# Arduino-Pro-Mini.net
KiCad netlist of a schematic drawn in EAGLE
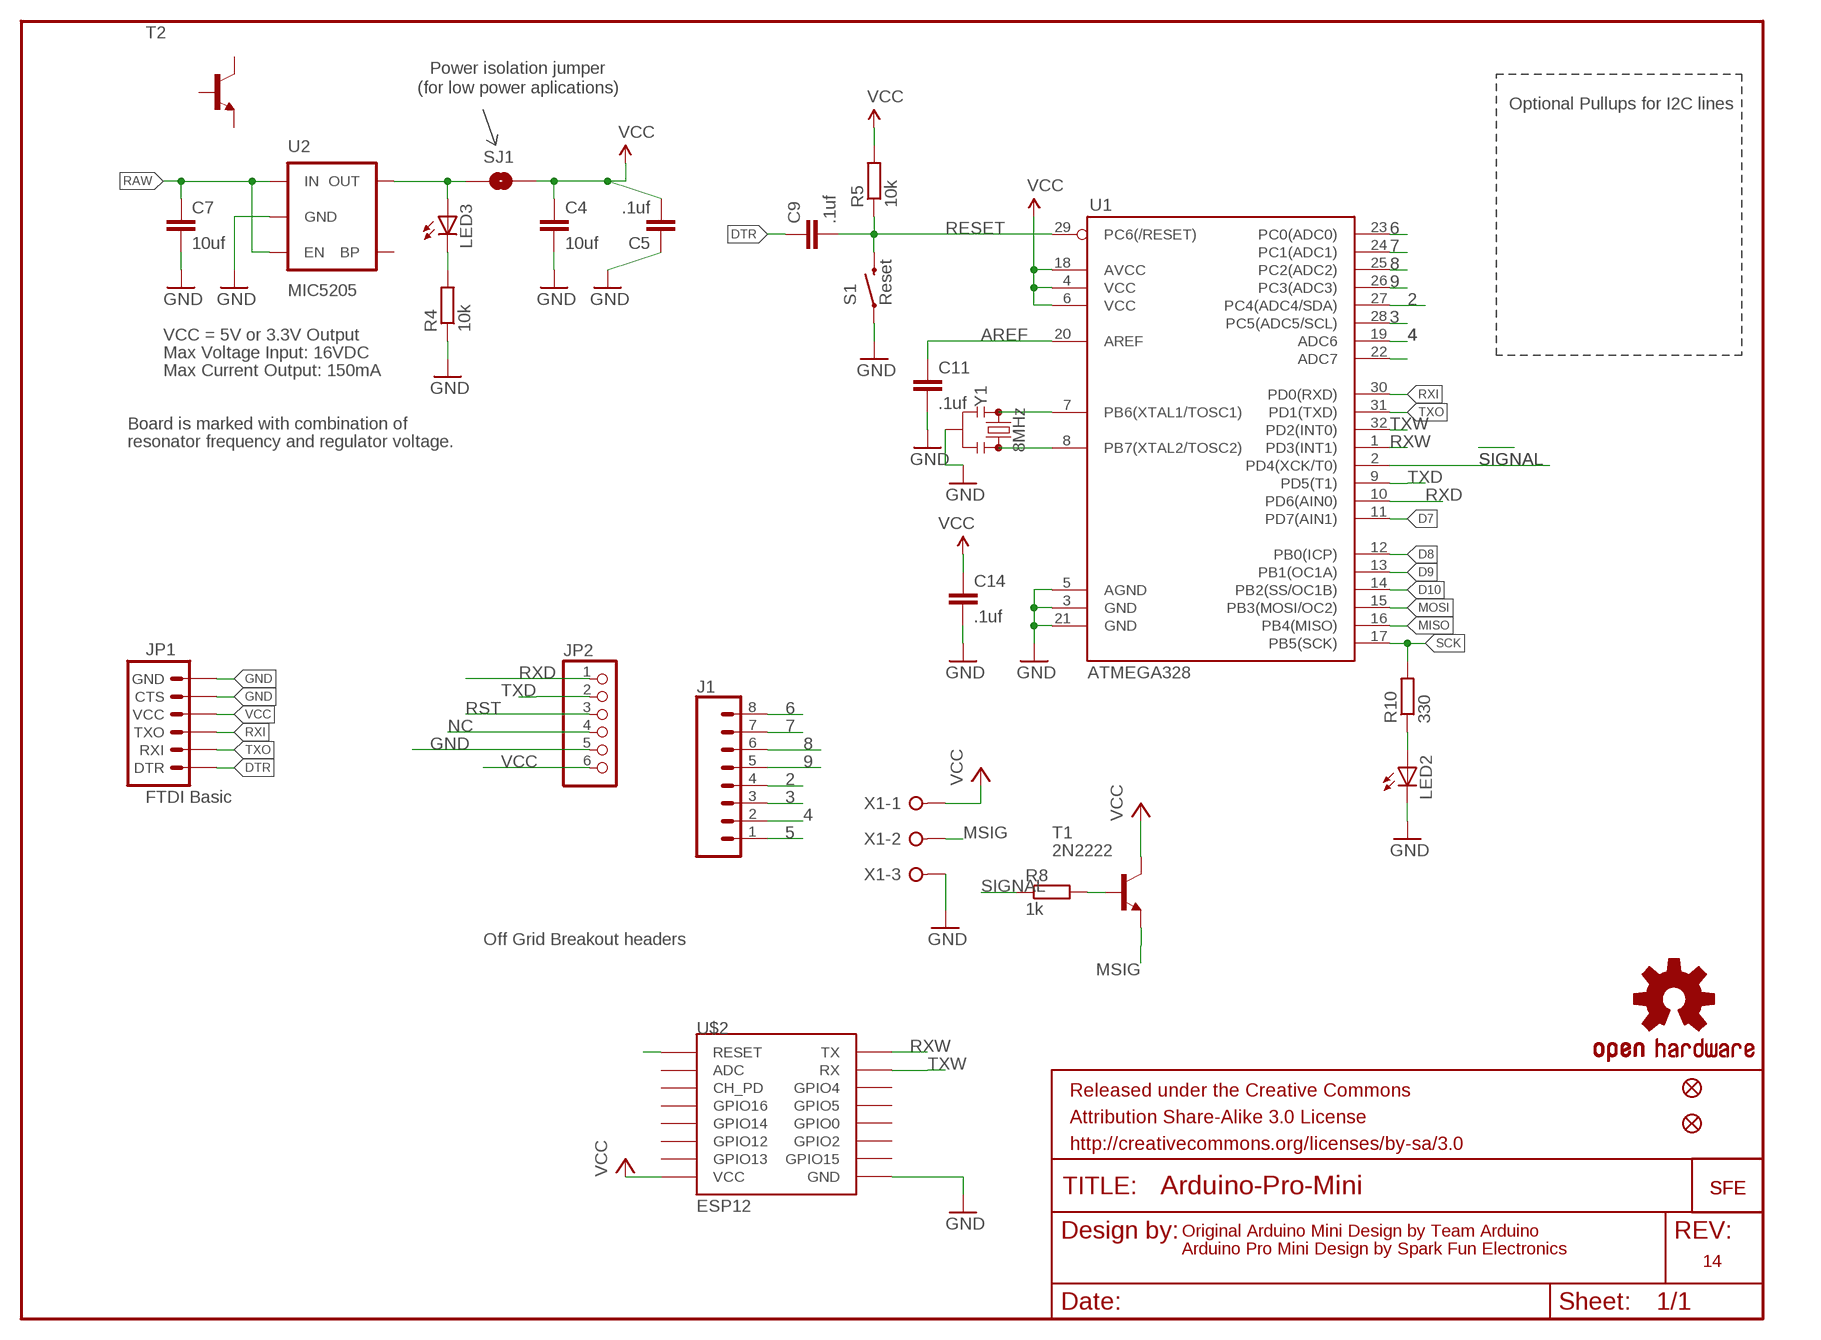
[diagram p0: schematic, sheet 1]

(export (version "E")
  (design (tool "Eeschema 10.0.6"))
  (components
    (comp (ref "C4")
      (value "10uf")
      (footprint "eagle-import:C1206")
      (libsource (lib "eagle-import") (part "C-EUC1206"))
    )
    (comp (ref "C5")
      (value ".1uf")
      (footprint "eagle-import:C1206")
      (libsource (lib "eagle-import") (part "C-EUC1206"))
    )
    (comp (ref "C7")
      (value "10uf")
      (footprint "eagle-import:C1206")
      (libsource (lib "eagle-import") (part "C-EUC1206"))
    )
    (comp (ref "C9")
      (value ".1uf")
      (footprint "eagle-import:C1206")
      (libsource (lib "eagle-import") (part "C-EUC1206"))
    )
    (comp (ref "C11")
      (value ".1uf")
      (footprint "eagle-import:C1206")
      (libsource (lib "eagle-import") (part "C-EUC1206"))
    )
    (comp (ref "C14")
      (value ".1uf")
      (footprint "eagle-import:C1206")
      (libsource (lib "eagle-import") (part "C-EUC1206"))
    )
    (comp (ref "FRAME1")
      (value "FRAME-LETTER")
      (footprint "eagle-import:CREATIVE_COMMONS")
      (libsource (lib "eagle-import") (part "FRAME-LETTER"))
    )
    (comp (ref "J1")
      (value "CONN_08\"")
      (footprint "eagle-import:1X08")
      (libsource (lib "eagle-import") (part "CONN_08{dblquote}"))
    )
    (comp (ref "JP1")
      (value "FTDI Basic")
      (footprint "eagle-import:1X06")
      (libsource (lib "eagle-import") (part "ARDUINO_SERIAL_PROGRAMPTH"))
    )
    (comp (ref "JP2")
      (value "PINHD-1X6")
      (footprint "eagle-import:1X06")
      (libsource (lib "eagle-import") (part "PINHD-1X6"))
    )
    (comp (ref "JP5")
      (value "FIDUCIALUFIDUCIAL")
      (footprint "eagle-import:MICRO-FIDUCIAL")
      (libsource (lib "eagle-import") (part "FIDUCIALUFIDUCIAL"))
    )
    (comp (ref "JP8")
      (value "FIDUCIALUFIDUCIAL")
      (footprint "eagle-import:MICRO-FIDUCIAL")
      (libsource (lib "eagle-import") (part "FIDUCIALUFIDUCIAL"))
    )
    (comp (ref "LED2")
      (value "LEDCHIPLED_1206")
      (footprint "eagle-import:CHIPLED_1206")
      (libsource (lib "eagle-import") (part "LEDCHIPLED_1206"))
    )
    (comp (ref "LED3")
      (value "LEDCHIPLED_1206")
      (footprint "eagle-import:CHIPLED_1206")
      (libsource (lib "eagle-import") (part "LEDCHIPLED_1206"))
    )
    (comp (ref "R4")
      (value "10k")
      (footprint "eagle-import:M1206")
      (libsource (lib "eagle-import") (part "R-EU_M1206"))
    )
    (comp (ref "R5")
      (value "10k")
      (footprint "eagle-import:M1206")
      (libsource (lib "eagle-import") (part "R-EU_M1206"))
    )
    (comp (ref "R8")
      (value "1k")
      (footprint "eagle-import:M1206")
      (libsource (lib "eagle-import") (part "R-EU_M1206"))
    )
    (comp (ref "R10")
      (value "330")
      (footprint "eagle-import:M1206")
      (libsource (lib "eagle-import") (part "R-EU_M1206"))
    )
    (comp (ref "S1")
      (value "Reset")
      (footprint "eagle-import:TACTILE-SWITCH-SMD-ALT01")
      (libsource (lib "eagle-import") (part "SWITCH-MOMENTARY-2SMD-ALT01"))
    )
    (comp (ref "SJ1")
      (value "SOLDERJUMPERNC")
      (footprint "eagle-import:SJ_2S")
      (libsource (lib "eagle-import") (part "SOLDERJUMPERNC"))
    )
    (comp (ref "T1")
      (value "2N2222")
      (footprint "eagle-import:TO92-EBC-OVAL")
      (libsource (lib "eagle-import") (part "2N2222"))
    )
    (comp (ref "T2")
      (value "-NPN-SOT223")
      (footprint "eagle-import:SOT223")
      (libsource (lib "eagle-import") (part "-NPN-SOT223"))
    )
    (comp (ref "U$1")
      (value "LOGO-SFESK")
      (footprint "eagle-import:SFE-LOGO-FLAME")
      (libsource (lib "eagle-import") (part "LOGO-SFESK"))
    )
    (comp (ref "U$2")
      (value "ESP12")
      (footprint "eagle-import:ESP12")
      (libsource (lib "eagle-import") (part "ESP12"))
    )
    (comp (ref "U$3")
      (value "OSHW-LOGOS")
      (footprint "eagle-import:OSHW-LOGO-S")
      (libsource (lib "eagle-import") (part "OSHW-LOGOS"))
    )
    (comp (ref "U$11")
      (value "LOGO-SFENEW")
      (footprint "eagle-import:SFE-NEW-WEBLOGO")
      (libsource (lib "eagle-import") (part "LOGO-SFENEW"))
    )
    (comp (ref "U1")
      (value "ATMEGA328")
      (footprint "eagle-import:TQFP32-08")
      (libsource (lib "eagle-import") (part "ATMEGA168"))
    )
    (comp (ref "U2")
      (value "MIC5205")
      (footprint "eagle-import:SOT23-5")
      (libsource (lib "eagle-import") (part "V_REG_LDOSMD"))
    )
    (comp (ref "X1")
      (value "W237-3E")
      (footprint "eagle-import:W237-3E")
      (libsource (lib "eagle-import") (part "W237-3E"))
    )
    (comp (ref "Y1")
      (value "8MHz")
      (footprint "eagle-import:RESONATOR-SMD-3.2X1.3")
      (libsource (lib "eagle-import") (part "RESONATOR-8MHZSMD_3.2X1.3"))
    )
  )
  (nets
    (net (code "1") (name "/2") (class "Default")
      (node (ref "J1") (pin "4") (pinfunction "4_4") (pintype "passive"))
      (node (ref "U1") (pin "27") (pinfunction "PC4(ADC4/SDA)_27") (pintype "bidirectional"))
    )
    (net (code "2") (name "/3") (class "Default")
      (node (ref "J1") (pin "3") (pinfunction "3_3") (pintype "passive"))
      (node (ref "U1") (pin "28") (pinfunction "PC5(ADC5/SCL)_28") (pintype "bidirectional"))
    )
    (net (code "3") (name "/4") (class "Default")
      (node (ref "J1") (pin "2") (pinfunction "2_2") (pintype "passive"))
      (node (ref "U1") (pin "19") (pinfunction "ADC6_19") (pintype "bidirectional"))
    )
    (net (code "4") (name "/5") (class "Default")
      (node (ref "J1") (pin "1") (pinfunction "1_1") (pintype "passive"))
      (node (ref "U1") (pin "22") (pinfunction "ADC7_22") (pintype "bidirectional"))
    )
    (net (code "5") (name "/6") (class "Default")
      (node (ref "J1") (pin "8") (pinfunction "8_8") (pintype "passive"))
      (node (ref "U1") (pin "23") (pinfunction "PC0(ADC0)_23") (pintype "bidirectional"))
    )
    (net (code "6") (name "/7") (class "Default")
      (node (ref "J1") (pin "7") (pinfunction "7_7") (pintype "passive"))
      (node (ref "U1") (pin "24") (pinfunction "PC1(ADC1)_24") (pintype "bidirectional"))
    )
    (net (code "7") (name "/8") (class "Default")
      (node (ref "J1") (pin "6") (pinfunction "6_6") (pintype "passive"))
      (node (ref "U1") (pin "25") (pinfunction "PC2(ADC2)_25") (pintype "bidirectional"))
    )
    (net (code "8") (name "/9") (class "Default")
      (node (ref "J1") (pin "5") (pinfunction "5_5") (pintype "passive"))
      (node (ref "U1") (pin "26") (pinfunction "PC3(ADC3)_26") (pintype "bidirectional"))
    )
    (net (code "9") (name "/AREF") (class "Default")
      (node (ref "C11") (pin "1") (pinfunction "1_1") (pintype "passive"))
      (node (ref "U1") (pin "20") (pinfunction "AREF_20") (pintype "bidirectional"))
    )
    (net (code "10") (name "/MSIG") (class "Default")
      (node (ref "X1") (pin "2") (pinfunction "KL_2") (pintype "passive"))
    )
    (net (code "11") (name "/NC") (class "Default")
      (node (ref "JP2") (pin "4") (pinfunction "4_4") (pintype "passive"))
    )
    (net (code "12") (name "/RESET") (class "Default")
      (node (ref "C9") (pin "2") (pinfunction "2_2") (pintype "passive"))
      (node (ref "R5") (pin "1") (pinfunction "1_1") (pintype "passive"))
      (node (ref "S1") (pin "3") (pinfunction "2_3") (pintype "passive"))
      (node (ref "S1") (pin "4") (pinfunction "2_4") (pintype "passive"))
      (node (ref "U1") (pin "29") (pinfunction "PC6(/RESET)_29") (pintype "bidirectional"))
    )
    (net (code "13") (name "/RST") (class "Default")
      (node (ref "JP2") (pin "3") (pinfunction "3_3") (pintype "passive"))
    )
    (net (code "14") (name "/RXD") (class "Default")
      (node (ref "JP2") (pin "1") (pinfunction "1_1") (pintype "passive"))
      (node (ref "U1") (pin "10") (pinfunction "PD6(AIN0)_10") (pintype "bidirectional"))
    )
    (net (code "15") (name "/RXW") (class "Default")
      (node (ref "U$2") (pin "TX") (pinfunction "TX_TX") (pintype "bidirectional"))
      (node (ref "U1") (pin "1") (pinfunction "PD3(INT1)_1") (pintype "bidirectional"))
    )
    (net (code "16") (name "/SIGNAL") (class "Default")
      (node (ref "U1") (pin "2") (pinfunction "PD4(XCK/T0)_2") (pintype "bidirectional"))
    )
    (net (code "17") (name "/TXD") (class "Default")
      (node (ref "JP2") (pin "2") (pinfunction "2_2") (pintype "passive"))
      (node (ref "U1") (pin "9") (pinfunction "PD5(T1)_9") (pintype "bidirectional"))
    )
    (net (code "18") (name "/TXW") (class "Default")
      (node (ref "U$2") (pin "RX") (pinfunction "RX_RX") (pintype "bidirectional"))
      (node (ref "U1") (pin "32") (pinfunction "PD2(INT0)_32") (pintype "bidirectional"))
    )
    (net (code "19") (name "D7") (class "Default")
      (node (ref "U1") (pin "11") (pinfunction "PD7(AIN1)_11") (pintype "bidirectional"))
    )
    (net (code "20") (name "D8") (class "Default")
      (node (ref "U1") (pin "12") (pinfunction "PB0(ICP)_12") (pintype "bidirectional"))
    )
    (net (code "21") (name "D9") (class "Default")
      (node (ref "U1") (pin "13") (pinfunction "PB1(OC1A)_13") (pintype "bidirectional"))
    )
    (net (code "22") (name "D10") (class "Default")
      (node (ref "U1") (pin "14") (pinfunction "PB2(SS/OC1B)_14") (pintype "bidirectional"))
    )
    (net (code "23") (name "DTR") (class "Default")
      (node (ref "C9") (pin "1") (pinfunction "1_1") (pintype "passive"))
      (node (ref "JP1") (pin "1") (pinfunction "DTR_1") (pintype "passive"))
    )
    (net (code "24") (name "GND") (class "Default")
      (node (ref "C11") (pin "2") (pinfunction "2_2") (pintype "passive"))
      (node (ref "C14") (pin "2") (pinfunction "2_2") (pintype "passive"))
      (node (ref "C4") (pin "2") (pinfunction "2_2") (pintype "passive"))
      (node (ref "C5") (pin "1") (pinfunction "1_1") (pintype "passive"))
      (node (ref "C7") (pin "2") (pinfunction "2_2") (pintype "passive"))
      (node (ref "JP1") (pin "5") (pinfunction "CTS_5") (pintype "passive"))
      (node (ref "JP1") (pin "6") (pinfunction "GND_6") (pintype "passive"))
      (node (ref "JP2") (pin "5") (pinfunction "5_5") (pintype "passive"))
      (node (ref "LED2") (pin "C") (pinfunction "C_C") (pintype "passive"))
      (node (ref "R4") (pin "1") (pinfunction "1_1") (pintype "passive"))
      (node (ref "S1") (pin "1") (pinfunction "1_1") (pintype "passive"))
      (node (ref "S1") (pin "2") (pinfunction "1_2") (pintype "passive"))
      (node (ref "U$2") (pin "GND") (pinfunction "GND_GND") (pintype "bidirectional"))
      (node (ref "U1") (pin "21") (pinfunction "GND_21") (pintype "bidirectional"))
      (node (ref "U1") (pin "3") (pinfunction "GND_3") (pintype "bidirectional"))
      (node (ref "U1") (pin "5") (pinfunction "AGND_5") (pintype "bidirectional"))
      (node (ref "U2") (pin "2") (pinfunction "GND_2") (pintype "input"))
      (node (ref "X1") (pin "3") (pinfunction "KL_3") (pintype "passive"))
      (node (ref "Y1") (pin "2") (pinfunction "2_2") (pintype "passive"))
    )
    (net (code "25") (name "MISO") (class "Default")
      (node (ref "U1") (pin "16") (pinfunction "PB4(MISO)_16") (pintype "bidirectional"))
    )
    (net (code "26") (name "MOSI") (class "Default")
      (node (ref "U1") (pin "15") (pinfunction "PB3(MOSI/OC2)_15") (pintype "bidirectional"))
    )
    (net (code "27") (name "Net-(LED2-PadA)") (class "Default")
      (node (ref "LED2") (pin "A") (pinfunction "A_A") (pintype "passive"))
      (node (ref "R10") (pin "1") (pinfunction "1_1") (pintype "passive"))
    )
    (net (code "28") (name "Net-(LED3-PadC)") (class "Default")
      (node (ref "LED3") (pin "C") (pinfunction "C_C") (pintype "passive"))
      (node (ref "R4") (pin "2") (pinfunction "2_2") (pintype "passive"))
    )
    (net (code "29") (name "Net-(R8-Pad2)") (class "Default")
      (node (ref "R8") (pin "2") (pinfunction "2_2") (pintype "passive"))
      (node (ref "T1") (pin "B") (pinfunction "B_B") (pintype "passive"))
    )
    (net (code "30") (name "Net-(U1-PB6(XTAL1{slash}TOSC1))") (class "Default")
      (node (ref "U1") (pin "7") (pinfunction "PB6(XTAL1/TOSC1)_7") (pintype "bidirectional"))
      (node (ref "Y1") (pin "1") (pinfunction "1_1") (pintype "passive"))
    )
    (net (code "31") (name "Net-(U1-PB7(XTAL2{slash}TOSC2))") (class "Default")
      (node (ref "U1") (pin "8") (pinfunction "PB7(XTAL2/TOSC2)_8") (pintype "bidirectional"))
      (node (ref "Y1") (pin "3") (pinfunction "3_3") (pintype "passive"))
    )
    (net (code "32") (name "Net-(U2-OUT)") (class "Default")
      (node (ref "LED3") (pin "A") (pinfunction "A_A") (pintype "passive"))
      (node (ref "SJ1") (pin "1") (pinfunction "1_1") (pintype "passive"))
      (node (ref "U2") (pin "5") (pinfunction "OUT_5") (pintype "passive"))
    )
    (net (code "33") (name "RAW") (class "Default")
      (node (ref "C7") (pin "1") (pinfunction "1_1") (pintype "passive"))
      (node (ref "U2") (pin "1") (pinfunction "IN_1") (pintype "input"))
      (node (ref "U2") (pin "3") (pinfunction "EN_3") (pintype "input"))
    )
    (net (code "34") (name "RXI") (class "Default")
      (node (ref "JP1") (pin "3") (pinfunction "TXO_3") (pintype "passive"))
      (node (ref "U1") (pin "30") (pinfunction "PD0(RXD)_30") (pintype "bidirectional"))
    )
    (net (code "35") (name "SCK") (class "Default")
      (node (ref "R10") (pin "2") (pinfunction "2_2") (pintype "passive"))
      (node (ref "U1") (pin "17") (pinfunction "PB5(SCK)_17") (pintype "bidirectional"))
    )
    (net (code "36") (name "TXO") (class "Default")
      (node (ref "JP1") (pin "2") (pinfunction "RXI_2") (pintype "passive"))
      (node (ref "U1") (pin "31") (pinfunction "PD1(TXD)_31") (pintype "bidirectional"))
    )
    (net (code "37") (name "VCC") (class "Default")
      (node (ref "C14") (pin "1") (pinfunction "1_1") (pintype "passive"))
      (node (ref "C4") (pin "1") (pinfunction "1_1") (pintype "passive"))
      (node (ref "C5") (pin "2") (pinfunction "2_2") (pintype "passive"))
      (node (ref "JP1") (pin "4") (pinfunction "VCC_4") (pintype "passive"))
      (node (ref "JP2") (pin "6") (pinfunction "6_6") (pintype "passive"))
      (node (ref "R5") (pin "2") (pinfunction "2_2") (pintype "passive"))
      (node (ref "SJ1") (pin "2") (pinfunction "2_2") (pintype "passive"))
      (node (ref "T1") (pin "C") (pinfunction "C_C") (pintype "passive"))
      (node (ref "U$2") (pin "VCC") (pinfunction "VCC_VCC") (pintype "bidirectional"))
      (node (ref "U1") (pin "18") (pinfunction "AVCC_18") (pintype "bidirectional"))
      (node (ref "U1") (pin "4") (pinfunction "VCC_4") (pintype "bidirectional"))
      (node (ref "U1") (pin "6") (pinfunction "VCC_6") (pintype "bidirectional"))
      (node (ref "X1") (pin "1") (pinfunction "KL_1") (pintype "passive"))
    )
    (net (code "38") (name "unconnected-(R8-Pad1)") (class "Default")
      (node (ref "R8") (pin "1") (pinfunction "1_1") (pintype "passive"))
    )
    (net (code "39") (name "unconnected-(T1-PadE)") (class "Default")
      (node (ref "T1") (pin "E") (pinfunction "E_E") (pintype "passive"))
    )
    (net (code "40") (name "unconnected-(T2-B-Pad1)") (class "Default")
      (node (ref "T2") (pin "1") (pinfunction "B_1") (pintype "passive"))
    )
    (net (code "41") (name "unconnected-(T2-C-Pad4)") (class "Default")
      (node (ref "T2") (pin "4") (pinfunction "C_4") (pintype "passive"))
    )
    (net (code "42") (name "unconnected-(T2-E-Pad3)") (class "Default")
      (node (ref "T2") (pin "3") (pinfunction "E_3") (pintype "passive"))
    )
    (net (code "43") (name "unconnected-(U$2-PadADC)") (class "Default")
      (node (ref "U$2") (pin "ADC") (pinfunction "ADC_ADC") (pintype "bidirectional"))
    )
    (net (code "44") (name "unconnected-(U$2-PadCH_PD)") (class "Default")
      (node (ref "U$2") (pin "CH_PD") (pinfunction "CH_PD_CH_PD") (pintype "bidirectional"))
    )
    (net (code "45") (name "unconnected-(U$2-PadGPIO0)") (class "Default")
      (node (ref "U$2") (pin "GPIO0") (pinfunction "GPIO0_GPIO0") (pintype "bidirectional"))
    )
    (net (code "46") (name "unconnected-(U$2-PadGPIO2)") (class "Default")
      (node (ref "U$2") (pin "GPIO2") (pinfunction "GPIO2_GPIO2") (pintype "bidirectional"))
    )
    (net (code "47") (name "unconnected-(U$2-PadGPIO4)") (class "Default")
      (node (ref "U$2") (pin "GPIO4") (pinfunction "GPIO4_GPIO4") (pintype "bidirectional"))
    )
    (net (code "48") (name "unconnected-(U$2-PadGPIO5)") (class "Default")
      (node (ref "U$2") (pin "GPIO5") (pinfunction "GPIO5_GPIO5") (pintype "bidirectional"))
    )
    (net (code "49") (name "unconnected-(U$2-PadGPIO12)") (class "Default")
      (node (ref "U$2") (pin "GPIO12") (pinfunction "GPIO12_GPIO12") (pintype "bidirectional"))
    )
    (net (code "50") (name "unconnected-(U$2-PadGPIO13)") (class "Default")
      (node (ref "U$2") (pin "GPIO13") (pinfunction "GPIO13_GPIO13") (pintype "bidirectional"))
    )
    (net (code "51") (name "unconnected-(U$2-PadGPIO14)") (class "Default")
      (node (ref "U$2") (pin "GPIO14") (pinfunction "GPIO14_GPIO14") (pintype "bidirectional"))
    )
    (net (code "52") (name "unconnected-(U$2-PadGPIO15)") (class "Default")
      (node (ref "U$2") (pin "GPIO15") (pinfunction "GPIO15_GPIO15") (pintype "bidirectional"))
    )
    (net (code "53") (name "unconnected-(U$2-PadGPIO16)") (class "Default")
      (node (ref "U$2") (pin "GPIO16") (pinfunction "GPIO16_GPIO16") (pintype "bidirectional"))
    )
    (net (code "54") (name "unconnected-(U$2-PadRESET)") (class "Default")
      (node (ref "U$2") (pin "RESET") (pinfunction "RESET_RESET") (pintype "bidirectional"))
    )
    (net (code "55") (name "unconnected-(U2-BP-Pad4)") (class "Default")
      (node (ref "U2") (pin "4") (pinfunction "BP_4") (pintype "input"))
    )
  )
)
